# V1.net
KiCad netlist of a schematic drawn in EAGLE
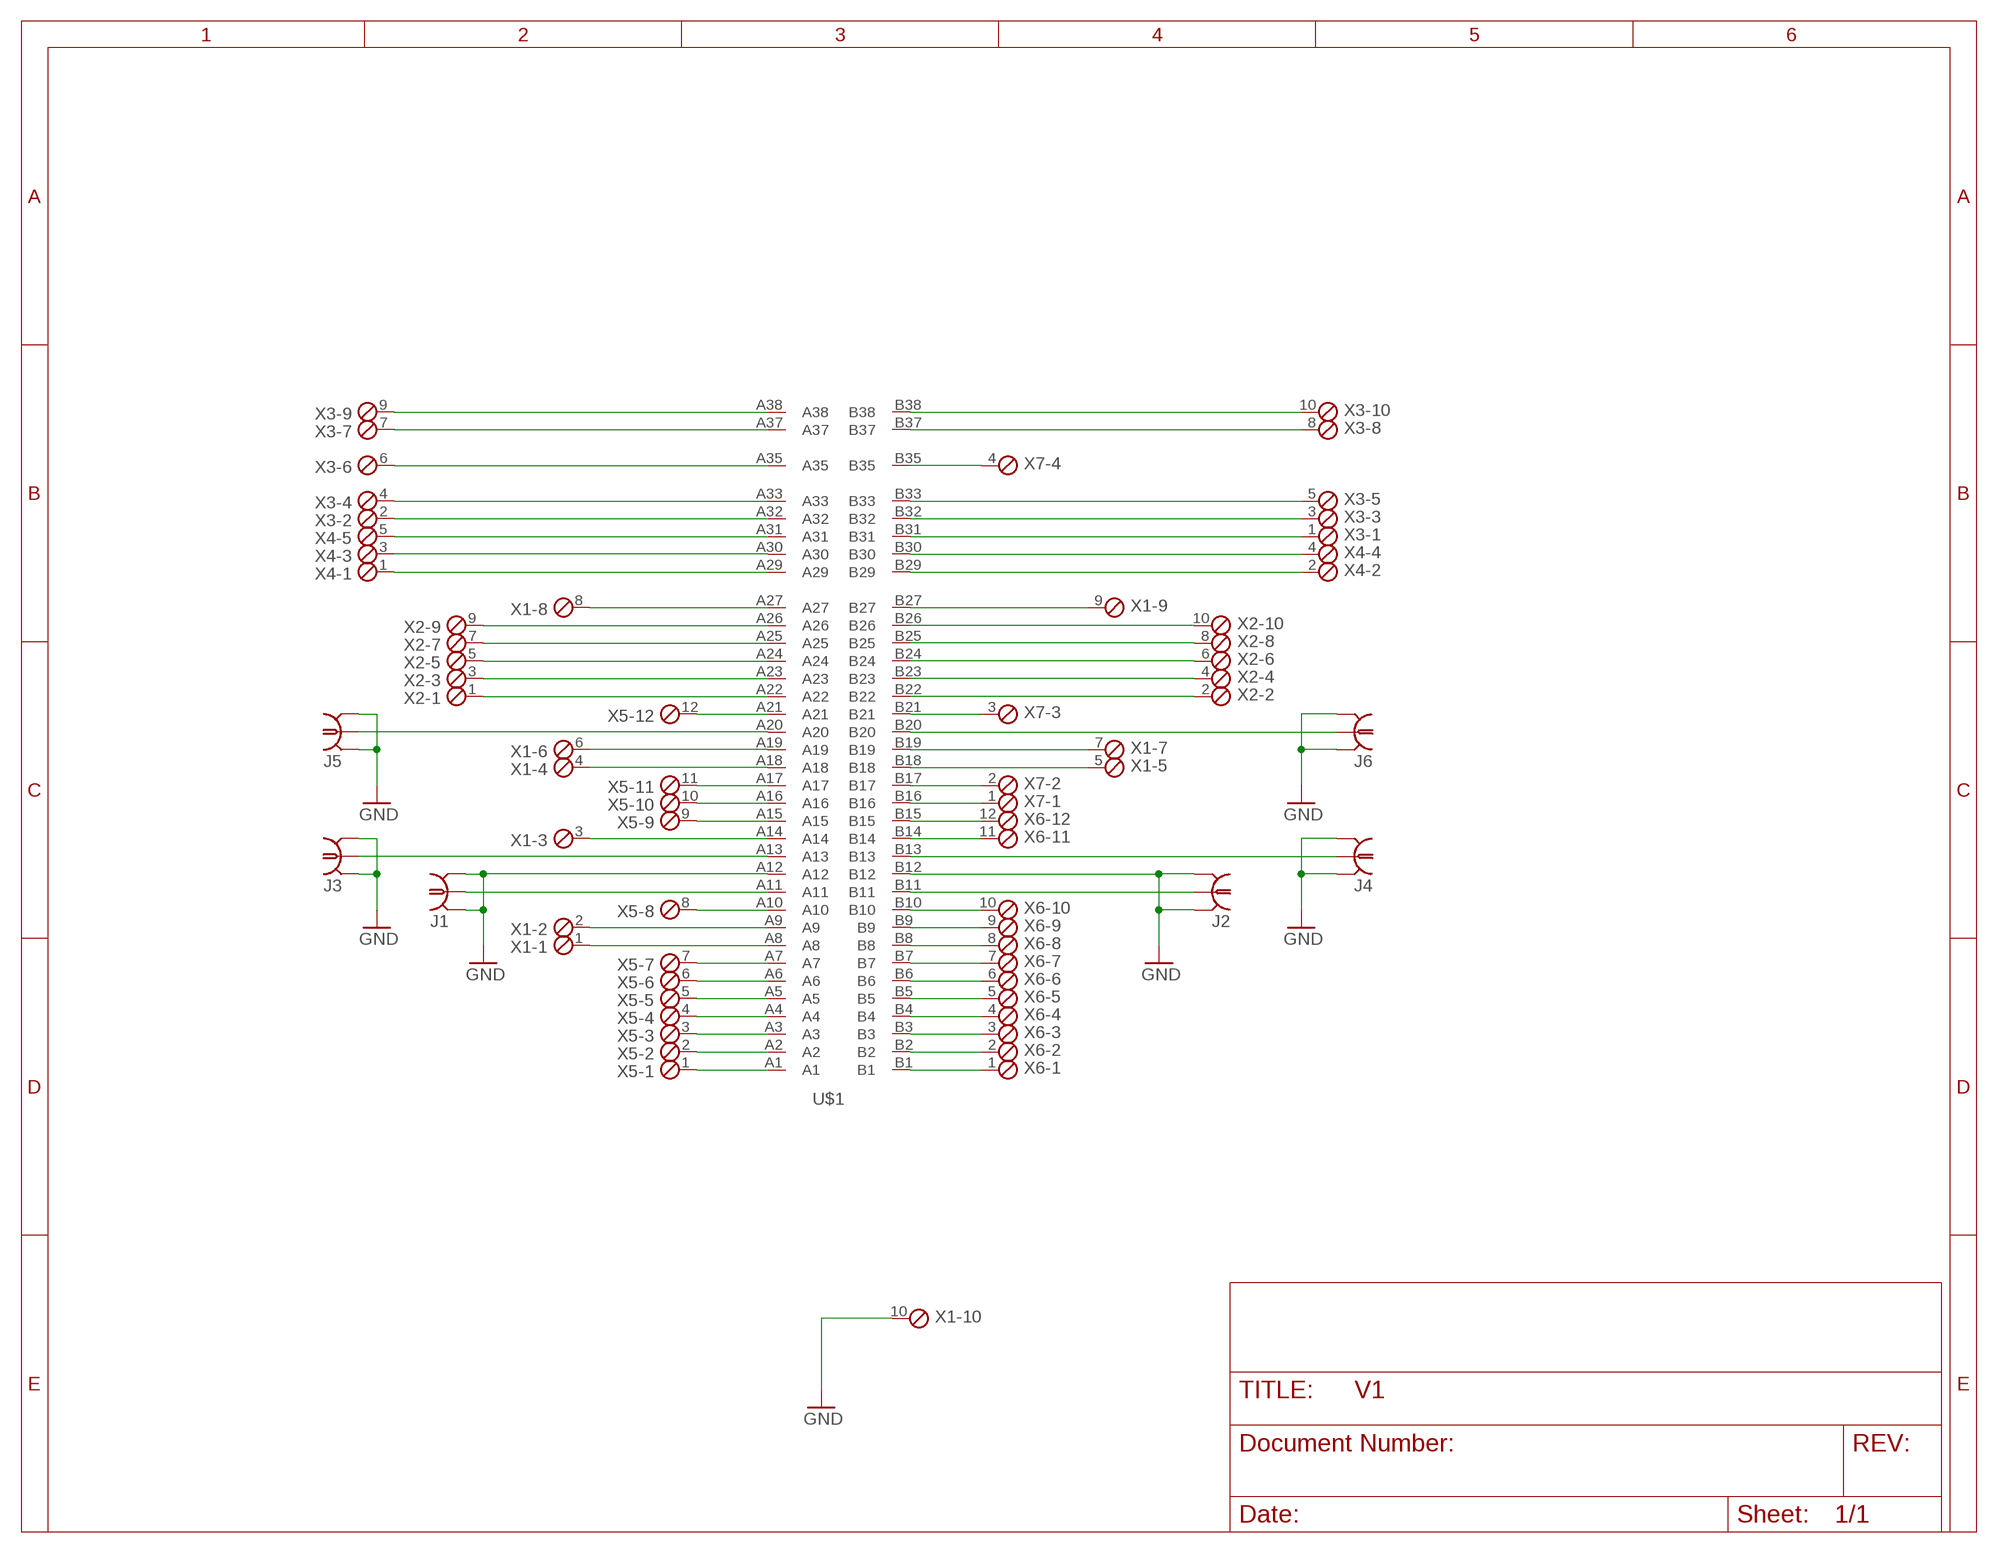
[diagram p0: schematic, sheet 1]

(export (version "E")
  (design (tool "Eeschema 10.0.6"))
  (components
    (comp (ref "J1")
      (value "BNC_MOLEX_73100")
      (footprint "eagle-import:73100")
      (libsource (lib "eagle-import") (part "BNC_MOLEX_73100"))
    )
    (comp (ref "J2")
      (value "BNC_MOLEX_73100")
      (footprint "eagle-import:73100")
      (libsource (lib "eagle-import") (part "BNC_MOLEX_73100"))
    )
    (comp (ref "J3")
      (value "BNC_MOLEX_73100")
      (footprint "eagle-import:73100")
      (libsource (lib "eagle-import") (part "BNC_MOLEX_73100"))
    )
    (comp (ref "J4")
      (value "BNC_MOLEX_73100")
      (footprint "eagle-import:73100")
      (libsource (lib "eagle-import") (part "BNC_MOLEX_73100"))
    )
    (comp (ref "J5")
      (value "BNC_MOLEX_73100")
      (footprint "eagle-import:73100")
      (libsource (lib "eagle-import") (part "BNC_MOLEX_73100"))
    )
    (comp (ref "J6")
      (value "BNC_MOLEX_73100")
      (footprint "eagle-import:73100")
      (libsource (lib "eagle-import") (part "BNC_MOLEX_73100"))
    )
    (comp (ref "U$1")
      (value "TEK_7000")
      (footprint "eagle-import:TEK_7000")
      (libsource (lib "eagle-import") (part "TEK_7000"))
    )
    (comp (ref "X1")
      (value "MPT10")
      (footprint "eagle-import:10POL254")
      (libsource (lib "eagle-import") (part "MPT10"))
    )
    (comp (ref "X2")
      (value "MPT10")
      (footprint "eagle-import:10POL254")
      (libsource (lib "eagle-import") (part "MPT10"))
    )
    (comp (ref "X3")
      (value "MPT10")
      (footprint "eagle-import:10POL254")
      (libsource (lib "eagle-import") (part "MPT10"))
    )
    (comp (ref "X4")
      (value "MPT5")
      (footprint "eagle-import:5POL254")
      (libsource (lib "eagle-import") (part "MPT5"))
    )
    (comp (ref "X5")
      (value "MPT12")
      (footprint "eagle-import:12POL254")
      (libsource (lib "eagle-import") (part "MPT12"))
    )
    (comp (ref "X6")
      (value "MPT12")
      (footprint "eagle-import:12POL254")
      (libsource (lib "eagle-import") (part "MPT12"))
    )
    (comp (ref "X7")
      (value "MPT4")
      (footprint "eagle-import:4POL254")
      (libsource (lib "eagle-import") (part "MPT4"))
    )
  )
  (nets
    (net (code "1") (name "GND") (class "Default")
      (node (ref "J1") (pin "GND") (pinfunction "GND_GND") (pintype "passive"))
      (node (ref "J1") (pin "GND@1") (pinfunction "GND_GND@1") (pintype "passive"))
      (node (ref "J2") (pin "GND") (pinfunction "GND_GND") (pintype "passive"))
      (node (ref "J2") (pin "GND@1") (pinfunction "GND_GND@1") (pintype "passive"))
      (node (ref "J3") (pin "GND") (pinfunction "GND_GND") (pintype "passive"))
      (node (ref "J3") (pin "GND@1") (pinfunction "GND_GND@1") (pintype "passive"))
      (node (ref "J4") (pin "GND") (pinfunction "GND_GND") (pintype "passive"))
      (node (ref "J4") (pin "GND@1") (pinfunction "GND_GND@1") (pintype "passive"))
      (node (ref "J5") (pin "GND") (pinfunction "GND_GND") (pintype "passive"))
      (node (ref "J5") (pin "GND@1") (pinfunction "GND_GND@1") (pintype "passive"))
      (node (ref "J6") (pin "GND") (pinfunction "GND_GND") (pintype "passive"))
      (node (ref "J6") (pin "GND@1") (pinfunction "GND_GND@1") (pintype "passive"))
      (node (ref "U$1") (pin "A12") (pinfunction "A12_A12") (pintype "bidirectional"))
      (node (ref "U$1") (pin "B12") (pinfunction "B12_B12") (pintype "bidirectional"))
      (node (ref "X1") (pin "10") (pinfunction "1_10") (pintype "passive"))
    )
    (net (code "2") (name "Net-(J1-PadSIG)") (class "Default")
      (node (ref "J1") (pin "SIG") (pinfunction "SIG_SIG") (pintype "passive"))
      (node (ref "U$1") (pin "A11") (pinfunction "A11_A11") (pintype "bidirectional"))
    )
    (net (code "3") (name "Net-(J2-PadSIG)") (class "Default")
      (node (ref "J2") (pin "SIG") (pinfunction "SIG_SIG") (pintype "passive"))
      (node (ref "U$1") (pin "B11") (pinfunction "B11_B11") (pintype "bidirectional"))
    )
    (net (code "4") (name "Net-(J3-PadSIG)") (class "Default")
      (node (ref "J3") (pin "SIG") (pinfunction "SIG_SIG") (pintype "passive"))
      (node (ref "U$1") (pin "A13") (pinfunction "A13_A13") (pintype "bidirectional"))
    )
    (net (code "5") (name "Net-(J4-PadSIG)") (class "Default")
      (node (ref "J4") (pin "SIG") (pinfunction "SIG_SIG") (pintype "passive"))
      (node (ref "U$1") (pin "B13") (pinfunction "B13_B13") (pintype "bidirectional"))
    )
    (net (code "6") (name "Net-(J5-PadSIG)") (class "Default")
      (node (ref "J5") (pin "SIG") (pinfunction "SIG_SIG") (pintype "passive"))
      (node (ref "U$1") (pin "A20") (pinfunction "A20_A20") (pintype "bidirectional"))
    )
    (net (code "7") (name "Net-(J6-PadSIG)") (class "Default")
      (node (ref "J6") (pin "SIG") (pinfunction "SIG_SIG") (pintype "passive"))
      (node (ref "U$1") (pin "B20") (pinfunction "B20_B20") (pintype "bidirectional"))
    )
    (net (code "8") (name "Net-(U$1-PadA1)") (class "Default")
      (node (ref "U$1") (pin "A1") (pinfunction "A1_A1") (pintype "bidirectional"))
      (node (ref "X5") (pin "1") (pinfunction "1_1") (pintype "passive"))
    )
    (net (code "9") (name "Net-(U$1-PadA8)") (class "Default")
      (node (ref "U$1") (pin "A8") (pinfunction "A8_A8") (pintype "bidirectional"))
      (node (ref "X1") (pin "1") (pinfunction "1_1") (pintype "passive"))
    )
    (net (code "10") (name "Net-(U$1-PadA22)") (class "Default")
      (node (ref "U$1") (pin "A22") (pinfunction "A22_A22") (pintype "bidirectional"))
      (node (ref "X2") (pin "1") (pinfunction "1_1") (pintype "passive"))
    )
    (net (code "11") (name "Net-(U$1-PadA29)") (class "Default")
      (node (ref "U$1") (pin "A29") (pinfunction "A29_A29") (pintype "bidirectional"))
      (node (ref "X4") (pin "1") (pinfunction "1_1") (pintype "passive"))
    )
    (net (code "12") (name "Net-(U$1-PadB1)") (class "Default")
      (node (ref "U$1") (pin "B1") (pinfunction "B1_B1") (pintype "bidirectional"))
      (node (ref "X6") (pin "1") (pinfunction "1_1") (pintype "passive"))
    )
    (net (code "13") (name "Net-(U$1-PadB16)") (class "Default")
      (node (ref "U$1") (pin "B16") (pinfunction "B16_B16") (pintype "bidirectional"))
      (node (ref "X7") (pin "1") (pinfunction "1_1") (pintype "passive"))
    )
    (net (code "14") (name "Net-(U$1-PadB31)") (class "Default")
      (node (ref "U$1") (pin "B31") (pinfunction "B31_B31") (pintype "bidirectional"))
      (node (ref "X3") (pin "1") (pinfunction "1_1") (pintype "passive"))
    )
    (net (code "15") (name "Net-(X1C-1)") (class "Default")
      (node (ref "U$1") (pin "A9") (pinfunction "A9_A9") (pintype "bidirectional"))
      (node (ref "X1") (pin "2") (pinfunction "1_2") (pintype "passive"))
    )
    (net (code "16") (name "Net-(X1D-1)") (class "Default")
      (node (ref "U$1") (pin "A14") (pinfunction "A14_A14") (pintype "bidirectional"))
      (node (ref "X1") (pin "3") (pinfunction "1_3") (pintype "passive"))
    )
    (net (code "17") (name "Net-(X1E-1)") (class "Default")
      (node (ref "U$1") (pin "A18") (pinfunction "A18_A18") (pintype "bidirectional"))
      (node (ref "X1") (pin "4") (pinfunction "1_4") (pintype "passive"))
    )
    (net (code "18") (name "Net-(X1F-1)") (class "Default")
      (node (ref "U$1") (pin "B18") (pinfunction "B18_B18") (pintype "bidirectional"))
      (node (ref "X1") (pin "5") (pinfunction "1_5") (pintype "passive"))
    )
    (net (code "19") (name "Net-(X1G-1)") (class "Default")
      (node (ref "U$1") (pin "A19") (pinfunction "A19_A19") (pintype "bidirectional"))
      (node (ref "X1") (pin "6") (pinfunction "1_6") (pintype "passive"))
    )
    (net (code "20") (name "Net-(X1H-1)") (class "Default")
      (node (ref "U$1") (pin "B19") (pinfunction "B19_B19") (pintype "bidirectional"))
      (node (ref "X1") (pin "7") (pinfunction "1_7") (pintype "passive"))
    )
    (net (code "21") (name "Net-(X1I-1)") (class "Default")
      (node (ref "U$1") (pin "A27") (pinfunction "A27_A27") (pintype "bidirectional"))
      (node (ref "X1") (pin "8") (pinfunction "1_8") (pintype "passive"))
    )
    (net (code "22") (name "Net-(X1J-1)") (class "Default")
      (node (ref "U$1") (pin "B27") (pinfunction "B27_B27") (pintype "bidirectional"))
      (node (ref "X1") (pin "9") (pinfunction "1_9") (pintype "passive"))
    )
    (net (code "23") (name "Net-(X2B-1)") (class "Default")
      (node (ref "U$1") (pin "B26") (pinfunction "B26_B26") (pintype "bidirectional"))
      (node (ref "X2") (pin "10") (pinfunction "1_10") (pintype "passive"))
    )
    (net (code "24") (name "Net-(X2C-1)") (class "Default")
      (node (ref "U$1") (pin "B22") (pinfunction "B22_B22") (pintype "bidirectional"))
      (node (ref "X2") (pin "2") (pinfunction "1_2") (pintype "passive"))
    )
    (net (code "25") (name "Net-(X2D-1)") (class "Default")
      (node (ref "U$1") (pin "A23") (pinfunction "A23_A23") (pintype "bidirectional"))
      (node (ref "X2") (pin "3") (pinfunction "1_3") (pintype "passive"))
    )
    (net (code "26") (name "Net-(X2E-1)") (class "Default")
      (node (ref "U$1") (pin "B23") (pinfunction "B23_B23") (pintype "bidirectional"))
      (node (ref "X2") (pin "4") (pinfunction "1_4") (pintype "passive"))
    )
    (net (code "27") (name "Net-(X2F-1)") (class "Default")
      (node (ref "U$1") (pin "A24") (pinfunction "A24_A24") (pintype "bidirectional"))
      (node (ref "X2") (pin "5") (pinfunction "1_5") (pintype "passive"))
    )
    (net (code "28") (name "Net-(X2G-1)") (class "Default")
      (node (ref "U$1") (pin "B24") (pinfunction "B24_B24") (pintype "bidirectional"))
      (node (ref "X2") (pin "6") (pinfunction "1_6") (pintype "passive"))
    )
    (net (code "29") (name "Net-(X2H-1)") (class "Default")
      (node (ref "U$1") (pin "A25") (pinfunction "A25_A25") (pintype "bidirectional"))
      (node (ref "X2") (pin "7") (pinfunction "1_7") (pintype "passive"))
    )
    (net (code "30") (name "Net-(X2I-1)") (class "Default")
      (node (ref "U$1") (pin "B25") (pinfunction "B25_B25") (pintype "bidirectional"))
      (node (ref "X2") (pin "8") (pinfunction "1_8") (pintype "passive"))
    )
    (net (code "31") (name "Net-(X2J-1)") (class "Default")
      (node (ref "U$1") (pin "A26") (pinfunction "A26_A26") (pintype "bidirectional"))
      (node (ref "X2") (pin "9") (pinfunction "1_9") (pintype "passive"))
    )
    (net (code "32") (name "Net-(X3B-1)") (class "Default")
      (node (ref "U$1") (pin "B38") (pinfunction "B38_B38") (pintype "bidirectional"))
      (node (ref "X3") (pin "10") (pinfunction "1_10") (pintype "passive"))
    )
    (net (code "33") (name "Net-(X3C-1)") (class "Default")
      (node (ref "U$1") (pin "A32") (pinfunction "A32_A32") (pintype "bidirectional"))
      (node (ref "X3") (pin "2") (pinfunction "1_2") (pintype "passive"))
    )
    (net (code "34") (name "Net-(X3D-1)") (class "Default")
      (node (ref "U$1") (pin "B32") (pinfunction "B32_B32") (pintype "bidirectional"))
      (node (ref "X3") (pin "3") (pinfunction "1_3") (pintype "passive"))
    )
    (net (code "35") (name "Net-(X3E-1)") (class "Default")
      (node (ref "U$1") (pin "A33") (pinfunction "A33_A33") (pintype "bidirectional"))
      (node (ref "X3") (pin "4") (pinfunction "1_4") (pintype "passive"))
    )
    (net (code "36") (name "Net-(X3F-1)") (class "Default")
      (node (ref "U$1") (pin "B33") (pinfunction "B33_B33") (pintype "bidirectional"))
      (node (ref "X3") (pin "5") (pinfunction "1_5") (pintype "passive"))
    )
    (net (code "37") (name "Net-(X3G-1)") (class "Default")
      (node (ref "U$1") (pin "A35") (pinfunction "A35_A35") (pintype "bidirectional"))
      (node (ref "X3") (pin "6") (pinfunction "1_6") (pintype "passive"))
    )
    (net (code "38") (name "Net-(X3H-1)") (class "Default")
      (node (ref "U$1") (pin "A37") (pinfunction "A37_A37") (pintype "bidirectional"))
      (node (ref "X3") (pin "7") (pinfunction "1_7") (pintype "passive"))
    )
    (net (code "39") (name "Net-(X3I-1)") (class "Default")
      (node (ref "U$1") (pin "B37") (pinfunction "B37_B37") (pintype "bidirectional"))
      (node (ref "X3") (pin "8") (pinfunction "1_8") (pintype "passive"))
    )
    (net (code "40") (name "Net-(X3J-1)") (class "Default")
      (node (ref "U$1") (pin "A38") (pinfunction "A38_A38") (pintype "bidirectional"))
      (node (ref "X3") (pin "9") (pinfunction "1_9") (pintype "passive"))
    )
    (net (code "41") (name "Net-(X4B-1)") (class "Default")
      (node (ref "U$1") (pin "B29") (pinfunction "B29_B29") (pintype "bidirectional"))
      (node (ref "X4") (pin "2") (pinfunction "1_2") (pintype "passive"))
    )
    (net (code "42") (name "Net-(X4C-1)") (class "Default")
      (node (ref "U$1") (pin "A30") (pinfunction "A30_A30") (pintype "bidirectional"))
      (node (ref "X4") (pin "3") (pinfunction "1_3") (pintype "passive"))
    )
    (net (code "43") (name "Net-(X4D-1)") (class "Default")
      (node (ref "U$1") (pin "B30") (pinfunction "B30_B30") (pintype "bidirectional"))
      (node (ref "X4") (pin "4") (pinfunction "1_4") (pintype "passive"))
    )
    (net (code "44") (name "Net-(X4E-1)") (class "Default")
      (node (ref "U$1") (pin "A31") (pinfunction "A31_A31") (pintype "bidirectional"))
      (node (ref "X4") (pin "5") (pinfunction "1_5") (pintype "passive"))
    )
    (net (code "45") (name "Net-(X5B-1)") (class "Default")
      (node (ref "U$1") (pin "A16") (pinfunction "A16_A16") (pintype "bidirectional"))
      (node (ref "X5") (pin "10") (pinfunction "1_10") (pintype "passive"))
    )
    (net (code "46") (name "Net-(X5C-1)") (class "Default")
      (node (ref "U$1") (pin "A17") (pinfunction "A17_A17") (pintype "bidirectional"))
      (node (ref "X5") (pin "11") (pinfunction "1_11") (pintype "passive"))
    )
    (net (code "47") (name "Net-(X5D-1)") (class "Default")
      (node (ref "U$1") (pin "A21") (pinfunction "A21_A21") (pintype "bidirectional"))
      (node (ref "X5") (pin "12") (pinfunction "1_12") (pintype "passive"))
    )
    (net (code "48") (name "Net-(X5E-1)") (class "Default")
      (node (ref "U$1") (pin "A2") (pinfunction "A2_A2") (pintype "bidirectional"))
      (node (ref "X5") (pin "2") (pinfunction "1_2") (pintype "passive"))
    )
    (net (code "49") (name "Net-(X5F-1)") (class "Default")
      (node (ref "U$1") (pin "A3") (pinfunction "A3_A3") (pintype "bidirectional"))
      (node (ref "X5") (pin "3") (pinfunction "1_3") (pintype "passive"))
    )
    (net (code "50") (name "Net-(X5G-1)") (class "Default")
      (node (ref "U$1") (pin "A4") (pinfunction "A4_A4") (pintype "bidirectional"))
      (node (ref "X5") (pin "4") (pinfunction "1_4") (pintype "passive"))
    )
    (net (code "51") (name "Net-(X5H-1)") (class "Default")
      (node (ref "U$1") (pin "A5") (pinfunction "A5_A5") (pintype "bidirectional"))
      (node (ref "X5") (pin "5") (pinfunction "1_5") (pintype "passive"))
    )
    (net (code "52") (name "Net-(X5I-1)") (class "Default")
      (node (ref "U$1") (pin "A6") (pinfunction "A6_A6") (pintype "bidirectional"))
      (node (ref "X5") (pin "6") (pinfunction "1_6") (pintype "passive"))
    )
    (net (code "53") (name "Net-(X5J-1)") (class "Default")
      (node (ref "U$1") (pin "A7") (pinfunction "A7_A7") (pintype "bidirectional"))
      (node (ref "X5") (pin "7") (pinfunction "1_7") (pintype "passive"))
    )
    (net (code "54") (name "Net-(X5K-1)") (class "Default")
      (node (ref "U$1") (pin "A10") (pinfunction "A10_A10") (pintype "bidirectional"))
      (node (ref "X5") (pin "8") (pinfunction "1_8") (pintype "passive"))
    )
    (net (code "55") (name "Net-(X5L-1)") (class "Default")
      (node (ref "U$1") (pin "A15") (pinfunction "A15_A15") (pintype "bidirectional"))
      (node (ref "X5") (pin "9") (pinfunction "1_9") (pintype "passive"))
    )
    (net (code "56") (name "Net-(X6B-1)") (class "Default")
      (node (ref "U$1") (pin "B10") (pinfunction "B10_B10") (pintype "bidirectional"))
      (node (ref "X6") (pin "10") (pinfunction "1_10") (pintype "passive"))
    )
    (net (code "57") (name "Net-(X6C-1)") (class "Default")
      (node (ref "U$1") (pin "B14") (pinfunction "B14_B14") (pintype "bidirectional"))
      (node (ref "X6") (pin "11") (pinfunction "1_11") (pintype "passive"))
    )
    (net (code "58") (name "Net-(X6D-1)") (class "Default")
      (node (ref "U$1") (pin "B15") (pinfunction "B15_B15") (pintype "bidirectional"))
      (node (ref "X6") (pin "12") (pinfunction "1_12") (pintype "passive"))
    )
    (net (code "59") (name "Net-(X6E-1)") (class "Default")
      (node (ref "U$1") (pin "B2") (pinfunction "B2_B2") (pintype "bidirectional"))
      (node (ref "X6") (pin "2") (pinfunction "1_2") (pintype "passive"))
    )
    (net (code "60") (name "Net-(X6F-1)") (class "Default")
      (node (ref "U$1") (pin "B3") (pinfunction "B3_B3") (pintype "bidirectional"))
      (node (ref "X6") (pin "3") (pinfunction "1_3") (pintype "passive"))
    )
    (net (code "61") (name "Net-(X6G-1)") (class "Default")
      (node (ref "U$1") (pin "B4") (pinfunction "B4_B4") (pintype "bidirectional"))
      (node (ref "X6") (pin "4") (pinfunction "1_4") (pintype "passive"))
    )
    (net (code "62") (name "Net-(X6H-1)") (class "Default")
      (node (ref "U$1") (pin "B5") (pinfunction "B5_B5") (pintype "bidirectional"))
      (node (ref "X6") (pin "5") (pinfunction "1_5") (pintype "passive"))
    )
    (net (code "63") (name "Net-(X6I-1)") (class "Default")
      (node (ref "U$1") (pin "B6") (pinfunction "B6_B6") (pintype "bidirectional"))
      (node (ref "X6") (pin "6") (pinfunction "1_6") (pintype "passive"))
    )
    (net (code "64") (name "Net-(X6J-1)") (class "Default")
      (node (ref "U$1") (pin "B7") (pinfunction "B7_B7") (pintype "bidirectional"))
      (node (ref "X6") (pin "7") (pinfunction "1_7") (pintype "passive"))
    )
    (net (code "65") (name "Net-(X6K-1)") (class "Default")
      (node (ref "U$1") (pin "B8") (pinfunction "B8_B8") (pintype "bidirectional"))
      (node (ref "X6") (pin "8") (pinfunction "1_8") (pintype "passive"))
    )
    (net (code "66") (name "Net-(X6L-1)") (class "Default")
      (node (ref "U$1") (pin "B9") (pinfunction "B9_B9") (pintype "bidirectional"))
      (node (ref "X6") (pin "9") (pinfunction "1_9") (pintype "passive"))
    )
    (net (code "67") (name "Net-(X7B-1)") (class "Default")
      (node (ref "U$1") (pin "B17") (pinfunction "B17_B17") (pintype "bidirectional"))
      (node (ref "X7") (pin "2") (pinfunction "1_2") (pintype "passive"))
    )
    (net (code "68") (name "Net-(X7C-1)") (class "Default")
      (node (ref "U$1") (pin "B21") (pinfunction "B21_B21") (pintype "bidirectional"))
      (node (ref "X7") (pin "3") (pinfunction "1_3") (pintype "passive"))
    )
    (net (code "69") (name "Net-(X7D-1)") (class "Default")
      (node (ref "U$1") (pin "B35") (pinfunction "B35_B35") (pintype "bidirectional"))
      (node (ref "X7") (pin "4") (pinfunction "1_4") (pintype "passive"))
    )
  )
)
